# Sheet1.net
KiCad netlist of a schematic drawn in Altium Designer
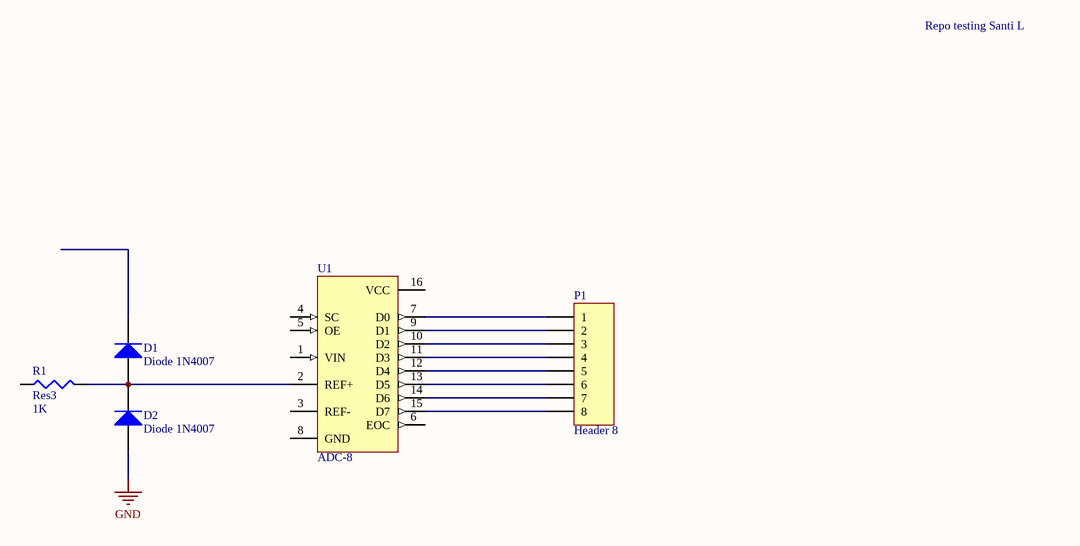
[diagram p0: Sheet1.SchDoc]

(export (version "E")
  (design (tool "Eeschema 10.0.6"))
  (components
    (comp (ref "D1")
      (value "Diode 1N4007")
      (footprint "DO-41")
      (description "1 Amp General Purpose Rectifier")
      (fields (field (name "PUBLISHER") "Altium Limited"))
      (libsource (lib "Miscellaneous Devices") (part "Diode 1N4007"))
    )
    (comp (ref "D2")
      (value "Diode 1N4007")
      (footprint "DO-41")
      (description "1 Amp General Purpose Rectifier")
      (fields (field (name "PUBLISHER") "Altium Limited"))
      (libsource (lib "Miscellaneous Devices") (part "Diode 1N4007"))
    )
    (comp (ref "P1")
      (value "Header 8")
      (footprint "HDR1X8")
      (description "Header, 8-Pin")
      (fields (field (name "PUBLISHER") "Altium Limited"))
      (libsource (lib "Miscellaneous Connectors") (part "Header 8"))
    )
    (comp (ref "R1")
      (value "Res3")
      (footprint "J1-0603")
      (description "Resistor")
      (fields (field (name "ALTIUM_VALUE") "1K") (field (name "PUBLISHER") "Altium Limited"))
      (libsource (lib "Miscellaneous Devices") (part "Res3"))
    )
    (comp (ref "U1")
      (value "ADC-8")
      (footprint "SOT403-1_N")
      (description "Generic 8-Bit A/D Converter")
      (fields (field (name "PUBLISHER") "Altium Limited"))
      (libsource (lib "Miscellaneous Devices") (part "ADC-8"))
    )
  )
  (nets
    (net (code "1") (name "GND") (class "Default")
      (node (ref "D2") (pin "1") (pinfunction "A_1") (pintype "passive"))
    )
    (net (code "2") (name "Net-(D1-A)") (class "Default")
      (node (ref "D1") (pin "1") (pinfunction "A_1") (pintype "passive"))
      (node (ref "D2") (pin "2") (pinfunction "K_2") (pintype "passive"))
      (node (ref "R1") (pin "2") (pinfunction "2_2") (pintype "passive"))
      (node (ref "U1") (pin "2") (pinfunction "REF+_2") (pintype "passive"))
    )
    (net (code "3") (name "Net-(U1-D0)") (class "Default")
      (node (ref "P1") (pin "1") (pinfunction "1_1") (pintype "passive"))
      (node (ref "U1") (pin "7") (pinfunction "D0_7") (pintype "output"))
    )
    (net (code "4") (name "Net-(U1-D1)") (class "Default")
      (node (ref "P1") (pin "2") (pinfunction "2_2") (pintype "passive"))
      (node (ref "U1") (pin "9") (pinfunction "D1_9") (pintype "output"))
    )
    (net (code "5") (name "Net-(U1-D2)") (class "Default")
      (node (ref "P1") (pin "3") (pinfunction "3_3") (pintype "passive"))
      (node (ref "U1") (pin "10") (pinfunction "D2_10") (pintype "output"))
    )
    (net (code "6") (name "Net-(U1-D3)") (class "Default")
      (node (ref "P1") (pin "4") (pinfunction "4_4") (pintype "passive"))
      (node (ref "U1") (pin "11") (pinfunction "D3_11") (pintype "output"))
    )
    (net (code "7") (name "Net-(U1-D4)") (class "Default")
      (node (ref "P1") (pin "5") (pinfunction "5_5") (pintype "passive"))
      (node (ref "U1") (pin "12") (pinfunction "D4_12") (pintype "output"))
    )
    (net (code "8") (name "Net-(U1-D5)") (class "Default")
      (node (ref "P1") (pin "6") (pinfunction "6_6") (pintype "passive"))
      (node (ref "U1") (pin "13") (pinfunction "D5_13") (pintype "output"))
    )
    (net (code "9") (name "Net-(U1-D6)") (class "Default")
      (node (ref "P1") (pin "7") (pinfunction "7_7") (pintype "passive"))
      (node (ref "U1") (pin "14") (pinfunction "D6_14") (pintype "output"))
    )
    (net (code "10") (name "Net-(U1-D7)") (class "Default")
      (node (ref "P1") (pin "8") (pinfunction "8_8") (pintype "passive"))
      (node (ref "U1") (pin "15") (pinfunction "D7_15") (pintype "output"))
    )
    (net (code "11") (name "unconnected-(D1-K-Pad2)") (class "Default")
      (node (ref "D1") (pin "2") (pinfunction "K_2") (pintype "passive"))
    )
    (net (code "12") (name "unconnected-(R1-Pad1)") (class "Default")
      (node (ref "R1") (pin "1") (pinfunction "1_1") (pintype "passive"))
    )
    (net (code "13") (name "unconnected-(U1-EOC-Pad6)") (class "Default")
      (node (ref "U1") (pin "6") (pinfunction "EOC_6") (pintype "output"))
    )
    (net (code "14") (name "unconnected-(U1-GND-Pad8)") (class "Default")
      (node (ref "U1") (pin "8") (pinfunction "GND_8") (pintype "power_in"))
    )
    (net (code "15") (name "unconnected-(U1-OE-Pad5)") (class "Default")
      (node (ref "U1") (pin "5") (pinfunction "OE_5") (pintype "input"))
    )
    (net (code "16") (name "unconnected-(U1-REF--Pad3)") (class "Default")
      (node (ref "U1") (pin "3") (pinfunction "REF-_3") (pintype "passive"))
    )
    (net (code "17") (name "unconnected-(U1-SC-Pad4)") (class "Default")
      (node (ref "U1") (pin "4") (pinfunction "SC_4") (pintype "input"))
    )
    (net (code "18") (name "unconnected-(U1-VCC-Pad16)") (class "Default")
      (node (ref "U1") (pin "16") (pinfunction "VCC_16") (pintype "power_in"))
    )
    (net (code "19") (name "unconnected-(U1-VIN-Pad1)") (class "Default")
      (node (ref "U1") (pin "1") (pinfunction "VIN_1") (pintype "input"))
    )
  )
)
